# conn_ffc_ws22_12pin.net
KiCad netlist of a schematic drawn in Altium Designer
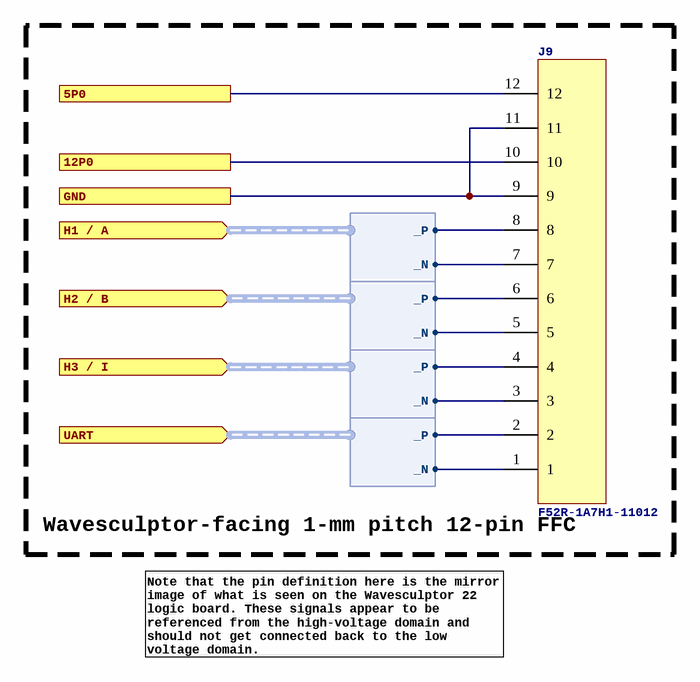
[diagram p0: conn_ffc_ws22_12pin.SchDoc]

(export (version "E")
  (design (tool "Eeschema 10.0.6"))
  (components
    (comp (ref "J9")
      (value "F52R-1A7H1-11012")
      (footprint "AMPHENOL_F52R-1A7H1-11012")
      (description "FPC/FFC Connector Socket 12 Position 1mm Bottom Contact Solder Right Angle Surface Mount T/R")
      (fields (field (name "MANUFACTURER") "Amphenol ICC / FCI"))
      (libsource (lib "SSCP") (part "CONN_AMPHENOL_FPC_F52R-1A7H1-11012"))
    )
  )
  (nets
    (net (code "2") (name "/5P0") (class "Default")
      (node (ref "J9") (pin "12") (pinfunction "12_12") (pintype "passive"))
    )
    (net (code "3") (name "/12P0") (class "Default")
      (node (ref "J9") (pin "10") (pinfunction "10_10") (pintype "passive"))
    )
    (net (code "4") (name "/GND") (class "Default")
      (node (ref "J9") (pin "11") (pinfunction "11_11") (pintype "passive"))
      (node (ref "J9") (pin "9") (pinfunction "9_9") (pintype "passive"))
    )
    (net (code "7") (name "unconnected-(J9-Pad1)") (class "Default")
      (node (ref "J9") (pin "1") (pinfunction "1_1") (pintype "passive"))
    )
    (net (code "8") (name "unconnected-(J9-Pad2)") (class "Default")
      (node (ref "J9") (pin "2") (pinfunction "2_2") (pintype "passive"))
    )
    (net (code "9") (name "unconnected-(J9-Pad3)") (class "Default")
      (node (ref "J9") (pin "3") (pinfunction "3_3") (pintype "passive"))
    )
    (net (code "10") (name "unconnected-(J9-Pad4)") (class "Default")
      (node (ref "J9") (pin "4") (pinfunction "4_4") (pintype "passive"))
    )
    (net (code "11") (name "unconnected-(J9-Pad5)") (class "Default")
      (node (ref "J9") (pin "5") (pinfunction "5_5") (pintype "passive"))
    )
    (net (code "12") (name "unconnected-(J9-Pad6)") (class "Default")
      (node (ref "J9") (pin "6") (pinfunction "6_6") (pintype "passive"))
    )
    (net (code "13") (name "unconnected-(J9-Pad7)") (class "Default")
      (node (ref "J9") (pin "7") (pinfunction "7_7") (pintype "passive"))
    )
    (net (code "14") (name "unconnected-(J9-Pad8)") (class "Default")
      (node (ref "J9") (pin "8") (pinfunction "8_8") (pintype "passive"))
    )
  )
)
